# msc3102.net
KiCad netlist of a schematic drawn in EAGLE
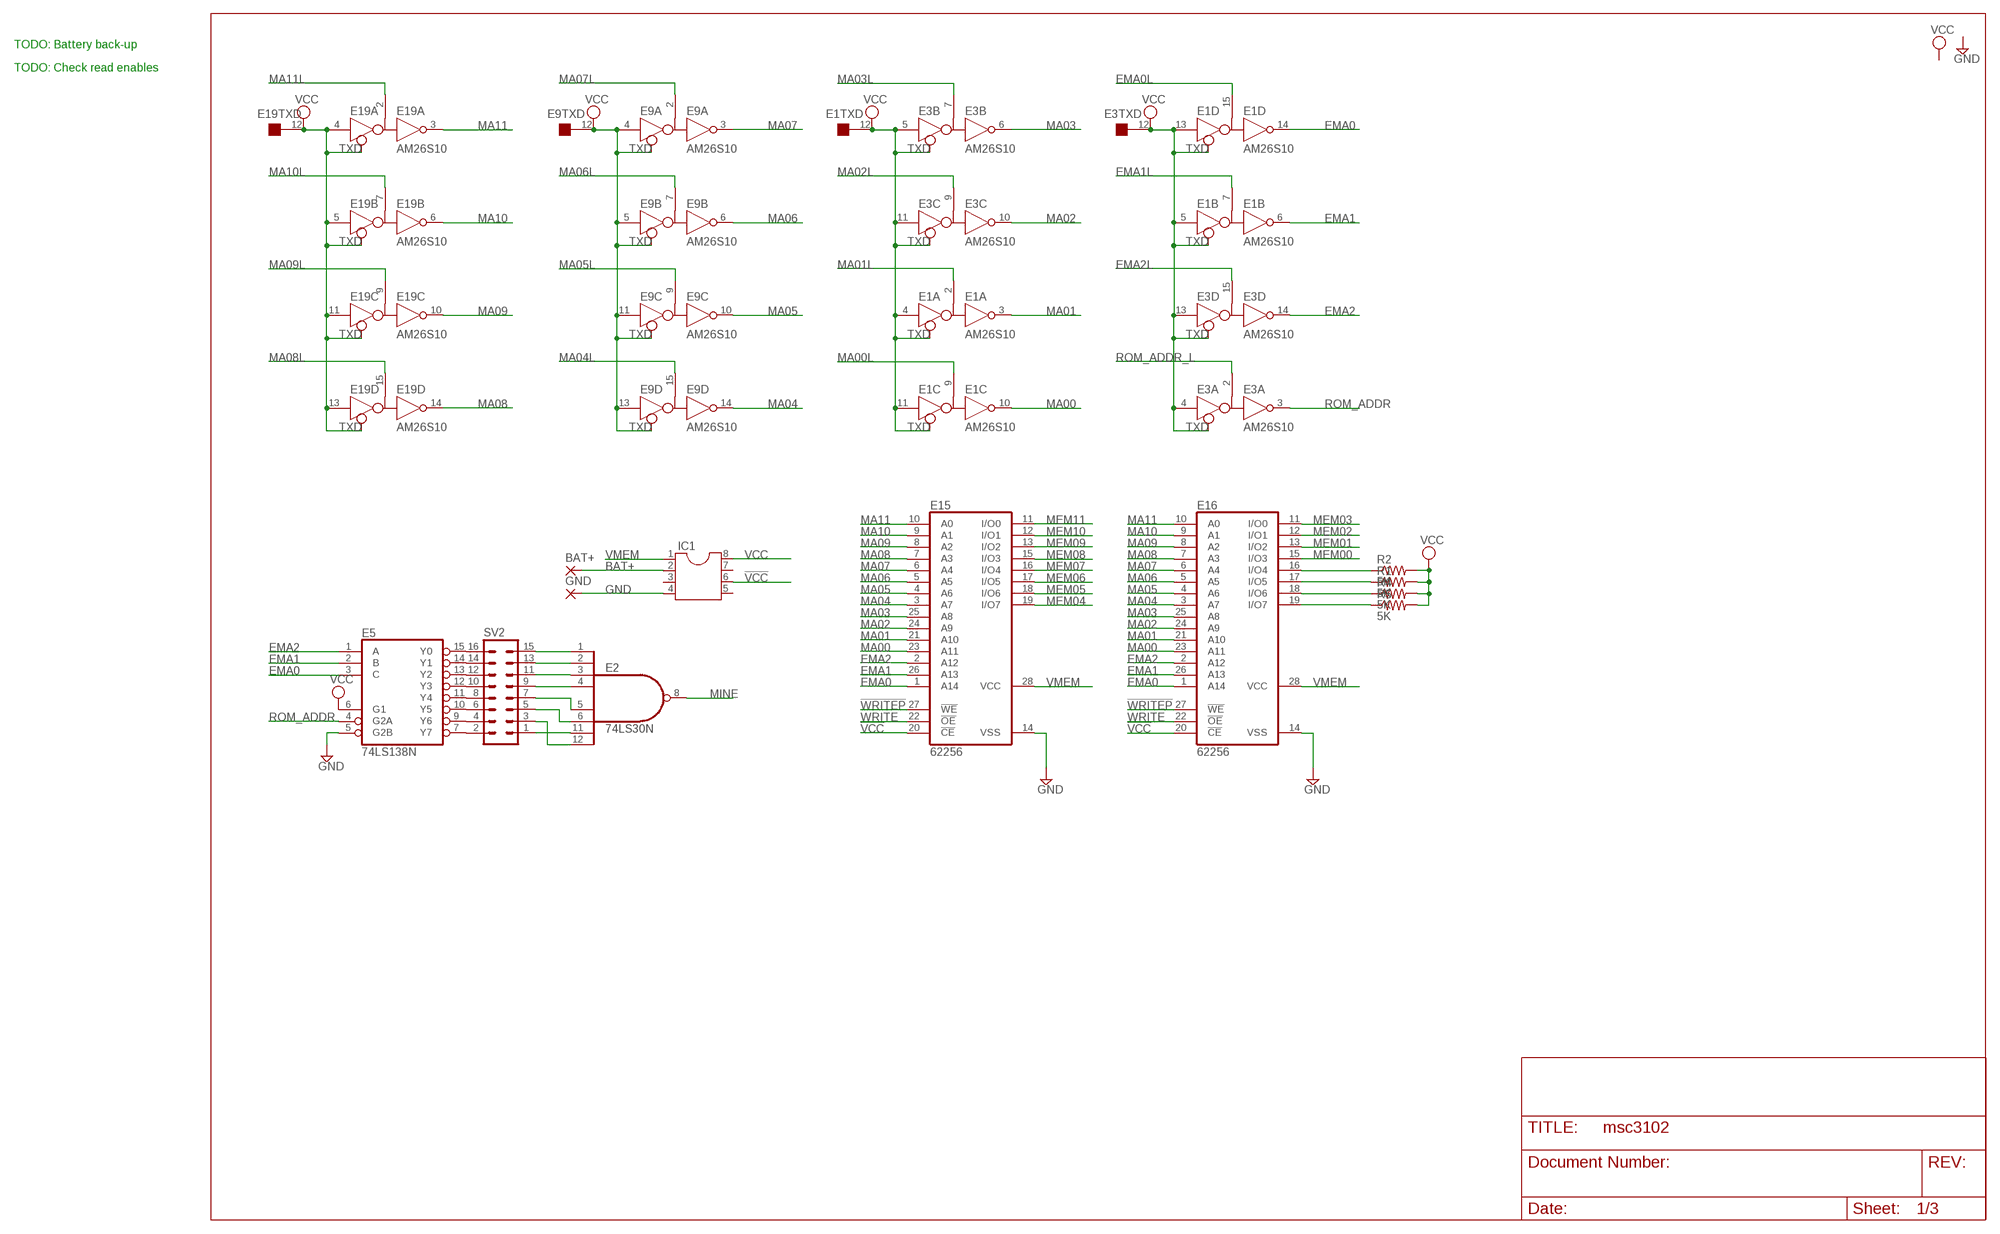
[diagram p0: schematic, sheet 1]
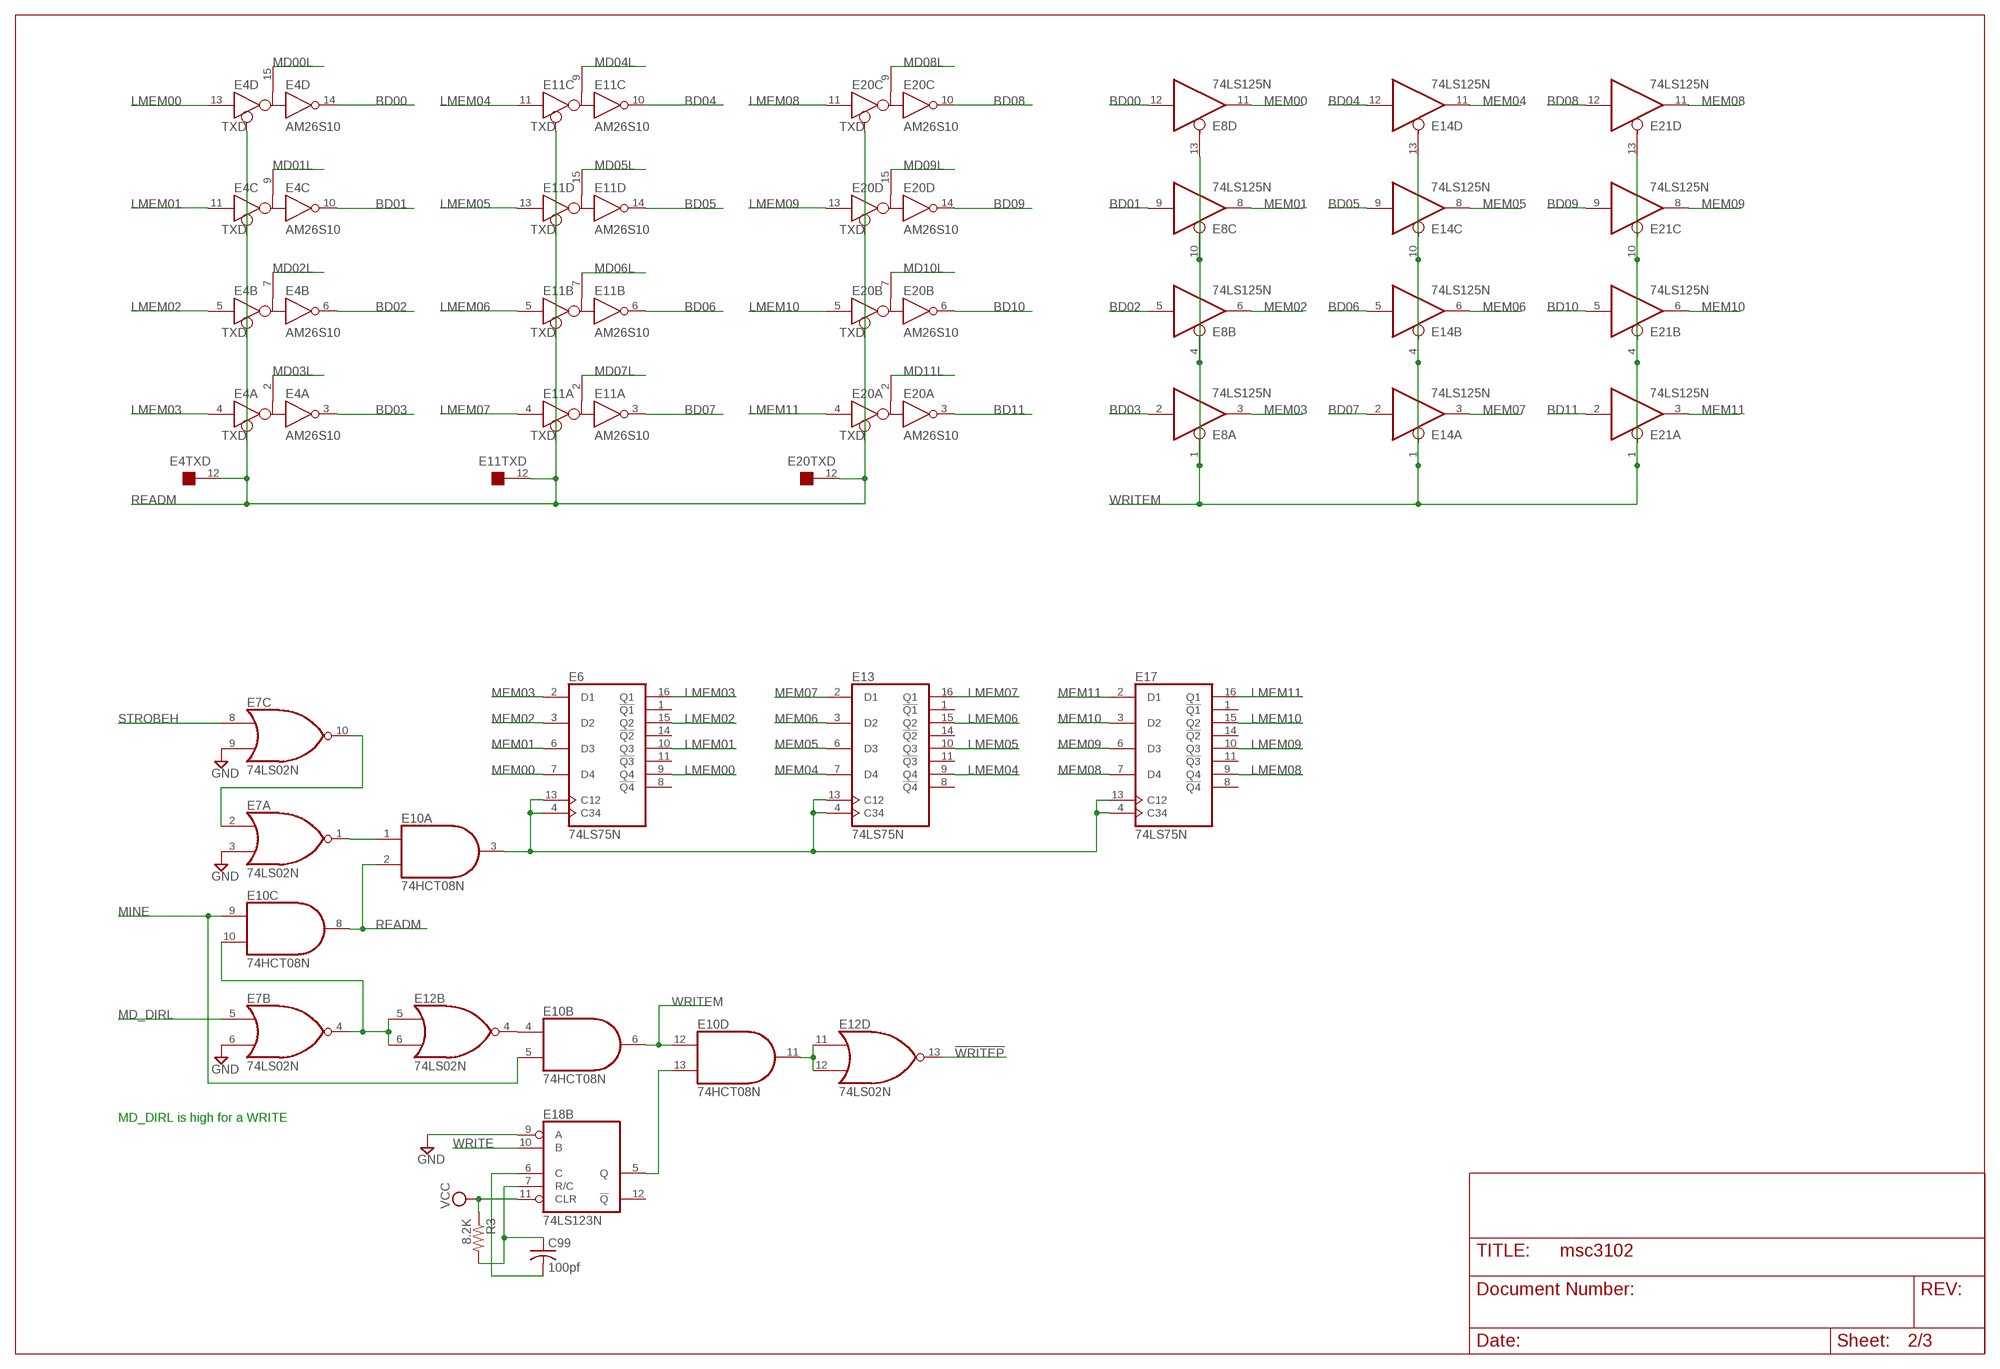
[diagram p1: schematic, sheet 2]
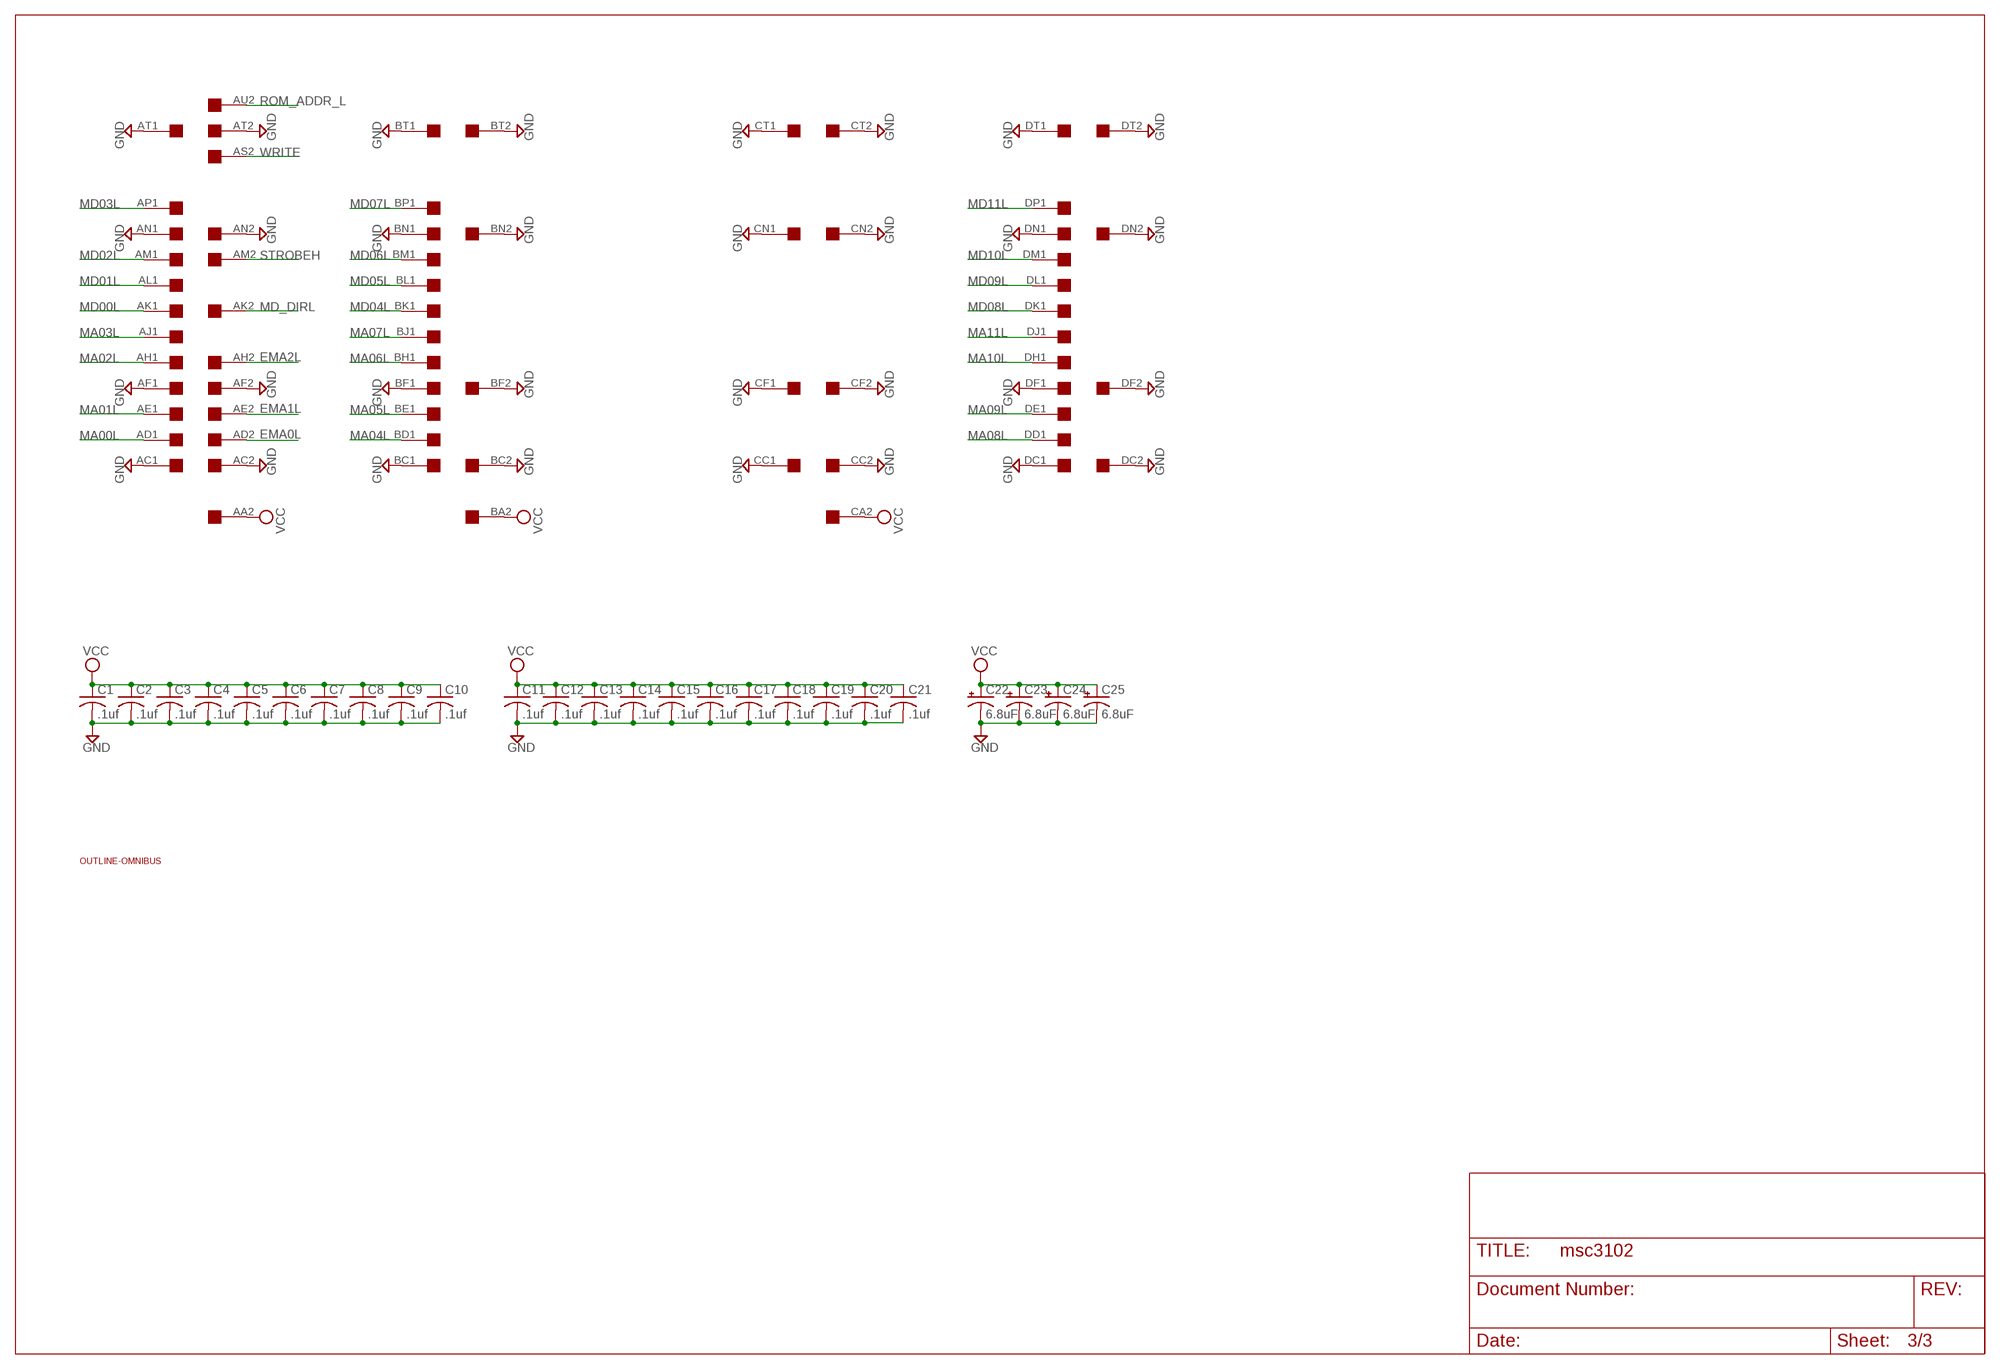
[diagram p2: schematic, sheet 3]

(export (version "E")
  (design (tool "Eeschema 10.0.6"))
  (components
    (comp (ref "C99")
      (value "100pf")
      (footprint "eagle-import:C050-025X075")
      (libsource (lib "eagle-import") (part "C-US050-025X075"))
    )
    (comp (ref "E4")
      (value "AM26S10")
      (footprint "eagle-import:DIL16")
      (libsource (lib "eagle-import") (part "AM26S10"))
    )
    (comp (ref "E6")
      (value "74LS75N")
      (footprint "eagle-import:DIL16")
      (libsource (lib "eagle-import") (part "7475NLS"))
    )
    (comp (ref "E7")
      (value "74LS02N")
      (footprint "eagle-import:DIL14")
      (libsource (lib "eagle-import") (part "7402NLS"))
    )
    (comp (ref "E8")
      (value "74LS125N")
      (footprint "eagle-import:DIL14")
      (libsource (lib "eagle-import") (part "74125NLS"))
    )
    (comp (ref "E10")
      (value "74HCT08N")
      (footprint "eagle-import:DIL14")
      (libsource (lib "eagle-import") (part "7408NLS"))
    )
    (comp (ref "E11")
      (value "AM26S10")
      (footprint "eagle-import:DIL16")
      (libsource (lib "eagle-import") (part "AM26S10"))
    )
    (comp (ref "E12")
      (value "74LS02N")
      (footprint "eagle-import:DIL14")
      (libsource (lib "eagle-import") (part "7402NLS"))
    )
    (comp (ref "E13")
      (value "74LS75N")
      (footprint "eagle-import:DIL16")
      (libsource (lib "eagle-import") (part "7475NLS"))
    )
    (comp (ref "E14")
      (value "74LS125N")
      (footprint "eagle-import:DIL14")
      (libsource (lib "eagle-import") (part "74125NLS"))
    )
    (comp (ref "E17")
      (value "74LS75N")
      (footprint "eagle-import:DIL16")
      (libsource (lib "eagle-import") (part "7475NLS"))
    )
    (comp (ref "E18")
      (value "74LS123N")
      (footprint "eagle-import:DIL16")
      (libsource (lib "eagle-import") (part "74123NLS"))
    )
    (comp (ref "E20")
      (value "AM26S10")
      (footprint "eagle-import:DIL16")
      (libsource (lib "eagle-import") (part "AM26S10"))
    )
    (comp (ref "E21")
      (value "74LS125N")
      (footprint "eagle-import:DIL14")
      (libsource (lib "eagle-import") (part "74125NLS"))
    )
    (comp (ref "R3")
      (value "8.2K")
      (footprint "eagle-import:0207_10")
      (libsource (lib "eagle-import") (part "R-US_0207/10"))
    )
    (comp (ref "BAT+")
      (value "2,15/1,0")
      (footprint "eagle-import:2,15_1,0")
      (libsource (lib "eagle-import") (part "2,15/1,0"))
    )
    (comp (ref "E1")
      (value "AM26S10")
      (footprint "eagle-import:DIL16")
      (libsource (lib "eagle-import") (part "AM26S10"))
    )
    (comp (ref "E2")
      (value "74LS30N")
      (footprint "eagle-import:DIL14")
      (libsource (lib "eagle-import") (part "7430NLS"))
    )
    (comp (ref "E3")
      (value "AM26S10")
      (footprint "eagle-import:DIL16")
      (libsource (lib "eagle-import") (part "AM26S10"))
    )
    (comp (ref "E5")
      (value "74LS138N")
      (footprint "eagle-import:DIL16")
      (libsource (lib "eagle-import") (part "74138NLS"))
    )
    (comp (ref "E9")
      (value "AM26S10")
      (footprint "eagle-import:DIL16")
      (libsource (lib "eagle-import") (part "AM26S10"))
    )
    (comp (ref "E15")
      (value "62256")
      (footprint "eagle-import:DIL28-6")
      (fields (field (name "MPN") "HN58C256AP85E"))
      (libsource (lib "eagle-import") (part "58C256P"))
    )
    (comp (ref "E16")
      (value "62256")
      (footprint "eagle-import:DIL28-6")
      (fields (field (name "MPN") "HN58C256AP85E"))
      (libsource (lib "eagle-import") (part "58C256P"))
    )
    (comp (ref "E19")
      (value "AM26S10")
      (footprint "eagle-import:DIL16")
      (libsource (lib "eagle-import") (part "AM26S10"))
    )
    (comp (ref "GND")
      (value "2,15/1,0")
      (footprint "eagle-import:2,15_1,0")
      (libsource (lib "eagle-import") (part "2,15/1,0"))
    )
    (comp (ref "IC1")
      (value "DIL8")
      (footprint "eagle-import:DIL08")
      (libsource (lib "eagle-import") (part "DIL8"))
    )
    (comp (ref "R1")
      (value "5K")
      (footprint "eagle-import:0207_10")
      (libsource (lib "eagle-import") (part "R-US_0207/10"))
    )
    (comp (ref "R2")
      (value "5K")
      (footprint "eagle-import:0207_10")
      (libsource (lib "eagle-import") (part "R-US_0207/10"))
    )
    (comp (ref "R4")
      (value "5K")
      (footprint "eagle-import:0207_10")
      (libsource (lib "eagle-import") (part "R-US_0207/10"))
    )
    (comp (ref "R5")
      (value "5K")
      (footprint "eagle-import:0207_10")
      (libsource (lib "eagle-import") (part "R-US_0207/10"))
    )
    (comp (ref "SV2")
      (value "MA08-2")
      (footprint "eagle-import:MA08-2")
      (libsource (lib "eagle-import") (part "MA08-2"))
    )
    (comp (ref "C1")
      (value ".1uf")
      (footprint "eagle-import:C050-025X075")
      (libsource (lib "eagle-import") (part "C-US050-025X075"))
    )
    (comp (ref "C2")
      (value ".1uf")
      (footprint "eagle-import:C050-025X075")
      (libsource (lib "eagle-import") (part "C-US050-025X075"))
    )
    (comp (ref "C3")
      (value ".1uf")
      (footprint "eagle-import:C050-025X075")
      (libsource (lib "eagle-import") (part "C-US050-025X075"))
    )
    (comp (ref "C4")
      (value ".1uf")
      (footprint "eagle-import:C050-025X075")
      (libsource (lib "eagle-import") (part "C-US050-025X075"))
    )
    (comp (ref "C5")
      (value ".1uf")
      (footprint "eagle-import:C050-025X075")
      (libsource (lib "eagle-import") (part "C-US050-025X075"))
    )
    (comp (ref "C6")
      (value ".1uf")
      (footprint "eagle-import:C050-025X075")
      (libsource (lib "eagle-import") (part "C-US050-025X075"))
    )
    (comp (ref "C7")
      (value ".1uf")
      (footprint "eagle-import:C050-025X075")
      (libsource (lib "eagle-import") (part "C-US050-025X075"))
    )
    (comp (ref "C8")
      (value ".1uf")
      (footprint "eagle-import:C050-025X075")
      (libsource (lib "eagle-import") (part "C-US050-025X075"))
    )
    (comp (ref "C9")
      (value ".1uf")
      (footprint "eagle-import:C050-025X075")
      (libsource (lib "eagle-import") (part "C-US050-025X075"))
    )
    (comp (ref "C10")
      (value ".1uf")
      (footprint "eagle-import:C050-025X075")
      (libsource (lib "eagle-import") (part "C-US050-025X075"))
    )
    (comp (ref "C11")
      (value ".1uf")
      (footprint "eagle-import:C050-025X075")
      (libsource (lib "eagle-import") (part "C-US050-025X075"))
    )
    (comp (ref "C12")
      (value ".1uf")
      (footprint "eagle-import:C050-025X075")
      (libsource (lib "eagle-import") (part "C-US050-025X075"))
    )
    (comp (ref "C13")
      (value ".1uf")
      (footprint "eagle-import:C050-025X075")
      (libsource (lib "eagle-import") (part "C-US050-025X075"))
    )
    (comp (ref "C14")
      (value ".1uf")
      (footprint "eagle-import:C050-025X075")
      (libsource (lib "eagle-import") (part "C-US050-025X075"))
    )
    (comp (ref "C15")
      (value ".1uf")
      (footprint "eagle-import:C050-025X075")
      (libsource (lib "eagle-import") (part "C-US050-025X075"))
    )
    (comp (ref "C16")
      (value ".1uf")
      (footprint "eagle-import:C050-025X075")
      (libsource (lib "eagle-import") (part "C-US050-025X075"))
    )
    (comp (ref "C17")
      (value ".1uf")
      (footprint "eagle-import:C050-025X075")
      (libsource (lib "eagle-import") (part "C-US050-025X075"))
    )
    (comp (ref "C18")
      (value ".1uf")
      (footprint "eagle-import:C050-025X075")
      (libsource (lib "eagle-import") (part "C-US050-025X075"))
    )
    (comp (ref "C19")
      (value ".1uf")
      (footprint "eagle-import:C050-025X075")
      (libsource (lib "eagle-import") (part "C-US050-025X075"))
    )
    (comp (ref "C20")
      (value ".1uf")
      (footprint "eagle-import:C050-025X075")
      (libsource (lib "eagle-import") (part "C-US050-025X075"))
    )
    (comp (ref "C21")
      (value ".1uf")
      (footprint "eagle-import:C050-025X075")
      (libsource (lib "eagle-import") (part "C-US050-025X075"))
    )
    (comp (ref "C22")
      (value "6.8uF")
      (footprint "eagle-import:E22-6")
      (libsource (lib "eagle-import") (part "CPOL-USE22-6AXIAL"))
    )
    (comp (ref "C23")
      (value "6.8uF")
      (footprint "eagle-import:E22-6")
      (libsource (lib "eagle-import") (part "CPOL-USE22-6AXIAL"))
    )
    (comp (ref "C24")
      (value "6.8uF")
      (footprint "eagle-import:E22-6")
      (libsource (lib "eagle-import") (part "CPOL-USE22-6AXIAL"))
    )
    (comp (ref "C25")
      (value "6.8uF")
      (footprint "eagle-import:E22-6")
      (libsource (lib "eagle-import") (part "CPOL-USE22-6AXIAL"))
    )
    (comp (ref "U$1")
      (value "OUTLINE-OMNIBUS")
      (footprint "eagle-import:OMNIBUS")
      (libsource (lib "eagle-import") (part "OUTLINE-OMNIBUS"))
    )
    (comp (ref "U$2")
      (value "QUAD")
      (footprint "eagle-import:EDGE-CON8")
      (libsource (lib "eagle-import") (part "QUAD"))
    )
  )
  (nets
    (net (code "1") (name "BAT+") (class "Default")
      (node (ref "BAT+") (pin "1") (pinfunction "P_1") (pintype "passive"))
      (node (ref "IC1") (pin "2") (pinfunction "2_2") (pintype "passive"))
    )
    (net (code "2") (name "BD00") (class "Default")
      (node (ref "E4") (pin "14") (pinfunction "R_14") (pintype "output"))
      (node (ref "E8") (pin "12") (pinfunction "I_12") (pintype "input"))
    )
    (net (code "3") (name "BD01") (class "Default")
      (node (ref "E4") (pin "10") (pinfunction "R_10") (pintype "output"))
      (node (ref "E8") (pin "9") (pinfunction "I_9") (pintype "input"))
    )
    (net (code "4") (name "BD02") (class "Default")
      (node (ref "E4") (pin "6") (pinfunction "R_6") (pintype "output"))
      (node (ref "E8") (pin "5") (pinfunction "I_5") (pintype "input"))
    )
    (net (code "5") (name "BD03") (class "Default")
      (node (ref "E4") (pin "3") (pinfunction "R_3") (pintype "output"))
      (node (ref "E8") (pin "2") (pinfunction "I_2") (pintype "input"))
    )
    (net (code "6") (name "BD04") (class "Default")
      (node (ref "E11") (pin "10") (pinfunction "R_10") (pintype "output"))
      (node (ref "E14") (pin "12") (pinfunction "I_12") (pintype "input"))
    )
    (net (code "7") (name "BD05") (class "Default")
      (node (ref "E11") (pin "14") (pinfunction "R_14") (pintype "output"))
      (node (ref "E14") (pin "9") (pinfunction "I_9") (pintype "input"))
    )
    (net (code "8") (name "BD06") (class "Default")
      (node (ref "E11") (pin "6") (pinfunction "R_6") (pintype "output"))
      (node (ref "E14") (pin "5") (pinfunction "I_5") (pintype "input"))
    )
    (net (code "9") (name "BD07") (class "Default")
      (node (ref "E11") (pin "3") (pinfunction "R_3") (pintype "output"))
      (node (ref "E14") (pin "2") (pinfunction "I_2") (pintype "input"))
    )
    (net (code "10") (name "BD08") (class "Default")
      (node (ref "E20") (pin "10") (pinfunction "R_10") (pintype "output"))
      (node (ref "E21") (pin "12") (pinfunction "I_12") (pintype "input"))
    )
    (net (code "11") (name "BD09") (class "Default")
      (node (ref "E20") (pin "14") (pinfunction "R_14") (pintype "output"))
      (node (ref "E21") (pin "9") (pinfunction "I_9") (pintype "input"))
    )
    (net (code "12") (name "BD10") (class "Default")
      (node (ref "E20") (pin "6") (pinfunction "R_6") (pintype "output"))
      (node (ref "E21") (pin "5") (pinfunction "I_5") (pintype "input"))
    )
    (net (code "13") (name "BD11") (class "Default")
      (node (ref "E20") (pin "3") (pinfunction "R_3") (pintype "output"))
      (node (ref "E21") (pin "2") (pinfunction "I_2") (pintype "input"))
    )
    (net (code "14") (name "EMA0") (class "Default")
      (node (ref "E1") (pin "14") (pinfunction "R_14") (pintype "output"))
      (node (ref "E15") (pin "1") (pinfunction "A14_1") (pintype "input"))
      (node (ref "E16") (pin "1") (pinfunction "A14_1") (pintype "input"))
      (node (ref "E5") (pin "3") (pinfunction "C_3") (pintype "input"))
    )
    (net (code "15") (name "EMA0L") (class "Default")
      (node (ref "E1") (pin "15") (pinfunction "B_15") (pintype "bidirectional"))
      (node (ref "U$2") (pin "AD2") (pinfunction "1_AD2") (pintype "bidirectional"))
    )
    (net (code "16") (name "EMA1") (class "Default")
      (node (ref "E1") (pin "6") (pinfunction "R_6") (pintype "output"))
      (node (ref "E15") (pin "26") (pinfunction "A13_26") (pintype "input"))
      (node (ref "E16") (pin "26") (pinfunction "A13_26") (pintype "input"))
      (node (ref "E5") (pin "2") (pinfunction "B_2") (pintype "input"))
    )
    (net (code "17") (name "EMA1L") (class "Default")
      (node (ref "E1") (pin "7") (pinfunction "B_7") (pintype "bidirectional"))
      (node (ref "U$2") (pin "AE2") (pinfunction "1_AE2") (pintype "bidirectional"))
    )
    (net (code "18") (name "EMA2") (class "Default")
      (node (ref "E15") (pin "2") (pinfunction "A12_2") (pintype "input"))
      (node (ref "E16") (pin "2") (pinfunction "A12_2") (pintype "input"))
      (node (ref "E3") (pin "14") (pinfunction "R_14") (pintype "output"))
      (node (ref "E5") (pin "1") (pinfunction "A_1") (pintype "input"))
    )
    (net (code "19") (name "EMA2L") (class "Default")
      (node (ref "E3") (pin "15") (pinfunction "B_15") (pintype "bidirectional"))
      (node (ref "U$2") (pin "AH2") (pinfunction "1_AH2") (pintype "bidirectional"))
    )
    (net (code "20") (name "GND") (class "Default")
      (node (ref "C1") (pin "2") (pinfunction "2_2") (pintype "passive"))
      (node (ref "C10") (pin "2") (pinfunction "2_2") (pintype "passive"))
      (node (ref "C11") (pin "2") (pinfunction "2_2") (pintype "passive"))
      (node (ref "C12") (pin "2") (pinfunction "2_2") (pintype "passive"))
      (node (ref "C13") (pin "2") (pinfunction "2_2") (pintype "passive"))
      (node (ref "C14") (pin "2") (pinfunction "2_2") (pintype "passive"))
      (node (ref "C15") (pin "2") (pinfunction "2_2") (pintype "passive"))
      (node (ref "C16") (pin "2") (pinfunction "2_2") (pintype "passive"))
      (node (ref "C17") (pin "2") (pinfunction "2_2") (pintype "passive"))
      (node (ref "C18") (pin "2") (pinfunction "2_2") (pintype "passive"))
      (node (ref "C19") (pin "2") (pinfunction "2_2") (pintype "passive"))
      (node (ref "C2") (pin "2") (pinfunction "2_2") (pintype "passive"))
      (node (ref "C20") (pin "2") (pinfunction "2_2") (pintype "passive"))
      (node (ref "C21") (pin "2") (pinfunction "2_2") (pintype "passive"))
      (node (ref "C22") (pin "-") (pinfunction "-_-") (pintype "passive"))
      (node (ref "C23") (pin "-") (pinfunction "-_-") (pintype "passive"))
      (node (ref "C24") (pin "-") (pinfunction "-_-") (pintype "passive"))
      (node (ref "C25") (pin "-") (pinfunction "-_-") (pintype "passive"))
      (node (ref "C3") (pin "2") (pinfunction "2_2") (pintype "passive"))
      (node (ref "C4") (pin "2") (pinfunction "2_2") (pintype "passive"))
      (node (ref "C5") (pin "2") (pinfunction "2_2") (pintype "passive"))
      (node (ref "C6") (pin "2") (pinfunction "2_2") (pintype "passive"))
      (node (ref "C7") (pin "2") (pinfunction "2_2") (pintype "passive"))
      (node (ref "C8") (pin "2") (pinfunction "2_2") (pintype "passive"))
      (node (ref "C9") (pin "2") (pinfunction "2_2") (pintype "passive"))
      (node (ref "E15") (pin "14") (pinfunction "VSS_14") (pintype "power_in"))
      (node (ref "E16") (pin "14") (pinfunction "VSS_14") (pintype "power_in"))
      (node (ref "E18") (pin "9") (pinfunction "A_9") (pintype "input"))
      (node (ref "E5") (pin "5") (pinfunction "G2B_5") (pintype "input"))
      (node (ref "E7") (pin "3") (pinfunction "I1_3") (pintype "input"))
      (node (ref "E7") (pin "6") (pinfunction "I1_6") (pintype "input"))
      (node (ref "E7") (pin "9") (pinfunction "I1_9") (pintype "input"))
      (node (ref "GND") (pin "1") (pinfunction "P_1") (pintype "passive"))
      (node (ref "IC1") (pin "4") (pinfunction "4_4") (pintype "passive"))
      (node (ref "U$2") (pin "AC1") (pinfunction "1_AC1") (pintype "bidirectional"))
      (node (ref "U$2") (pin "AC2") (pinfunction "1_AC2") (pintype "bidirectional"))
      (node (ref "U$2") (pin "AF1") (pinfunction "1_AF1") (pintype "bidirectional"))
      (node (ref "U$2") (pin "AF2") (pinfunction "1_AF2") (pintype "bidirectional"))
      (node (ref "U$2") (pin "AN1") (pinfunction "1_AN1") (pintype "bidirectional"))
      (node (ref "U$2") (pin "AN2") (pinfunction "1_AN2") (pintype "bidirectional"))
      (node (ref "U$2") (pin "AT1") (pinfunction "1_AT1") (pintype "bidirectional"))
      (node (ref "U$2") (pin "AT2") (pinfunction "1_AT2") (pintype "bidirectional"))
      (node (ref "U$2") (pin "BC1") (pinfunction "1_BC1") (pintype "bidirectional"))
      (node (ref "U$2") (pin "BC2") (pinfunction "1_BC2") (pintype "bidirectional"))
      (node (ref "U$2") (pin "BF1") (pinfunction "1_BF1") (pintype "bidirectional"))
      (node (ref "U$2") (pin "BF2") (pinfunction "1_BF2") (pintype "bidirectional"))
      (node (ref "U$2") (pin "BN1") (pinfunction "1_BN1") (pintype "bidirectional"))
      (node (ref "U$2") (pin "BN2") (pinfunction "1_BN2") (pintype "bidirectional"))
      (node (ref "U$2") (pin "BT1") (pinfunction "1_BT1") (pintype "bidirectional"))
      (node (ref "U$2") (pin "BT2") (pinfunction "1_BT2") (pintype "bidirectional"))
      (node (ref "U$2") (pin "CC1") (pinfunction "1_CC1") (pintype "bidirectional"))
      (node (ref "U$2") (pin "CC2") (pinfunction "1_CC2") (pintype "bidirectional"))
      (node (ref "U$2") (pin "CF1") (pinfunction "1_CF1") (pintype "bidirectional"))
      (node (ref "U$2") (pin "CF2") (pinfunction "1_CF2") (pintype "bidirectional"))
      (node (ref "U$2") (pin "CN1") (pinfunction "1_CN1") (pintype "bidirectional"))
      (node (ref "U$2") (pin "CN2") (pinfunction "1_CN2") (pintype "bidirectional"))
      (node (ref "U$2") (pin "CT1") (pinfunction "1_CT1") (pintype "bidirectional"))
      (node (ref "U$2") (pin "CT2") (pinfunction "1_CT2") (pintype "bidirectional"))
      (node (ref "U$2") (pin "DC1") (pinfunction "1_DC1") (pintype "bidirectional"))
      (node (ref "U$2") (pin "DC2") (pinfunction "1_DC2") (pintype "bidirectional"))
      (node (ref "U$2") (pin "DF1") (pinfunction "1_DF1") (pintype "bidirectional"))
      (node (ref "U$2") (pin "DF2") (pinfunction "1_DF2") (pintype "bidirectional"))
      (node (ref "U$2") (pin "DN1") (pinfunction "1_DN1") (pintype "bidirectional"))
      (node (ref "U$2") (pin "DN2") (pinfunction "1_DN2") (pintype "bidirectional"))
      (node (ref "U$2") (pin "DT1") (pinfunction "1_DT1") (pintype "bidirectional"))
      (node (ref "U$2") (pin "DT2") (pinfunction "1_DT2") (pintype "bidirectional"))
    )
    (net (code "21") (name "LMEM00") (class "Default")
      (node (ref "E4") (pin "13") (pinfunction "D_13") (pintype "input"))
      (node (ref "E6") (pin "9") (pinfunction "Q4_9") (pintype "output"))
    )
    (net (code "22") (name "LMEM01") (class "Default")
      (node (ref "E4") (pin "11") (pinfunction "D_11") (pintype "input"))
      (node (ref "E6") (pin "10") (pinfunction "Q3_10") (pintype "output"))
    )
    (net (code "23") (name "LMEM02") (class "Default")
      (node (ref "E4") (pin "5") (pinfunction "D_5") (pintype "input"))
      (node (ref "E6") (pin "15") (pinfunction "Q2_15") (pintype "output"))
    )
    (net (code "24") (name "LMEM03") (class "Default")
      (node (ref "E4") (pin "4") (pinfunction "D_4") (pintype "input"))
      (node (ref "E6") (pin "16") (pinfunction "Q1_16") (pintype "output"))
    )
    (net (code "25") (name "LMEM04") (class "Default")
      (node (ref "E11") (pin "11") (pinfunction "D_11") (pintype "input"))
      (node (ref "E13") (pin "9") (pinfunction "Q4_9") (pintype "output"))
    )
    (net (code "26") (name "LMEM05") (class "Default")
      (node (ref "E11") (pin "13") (pinfunction "D_13") (pintype "input"))
      (node (ref "E13") (pin "10") (pinfunction "Q3_10") (pintype "output"))
    )
    (net (code "27") (name "LMEM06") (class "Default")
      (node (ref "E11") (pin "5") (pinfunction "D_5") (pintype "input"))
      (node (ref "E13") (pin "15") (pinfunction "Q2_15") (pintype "output"))
    )
    (net (code "28") (name "LMEM07") (class "Default")
      (node (ref "E11") (pin "4") (pinfunction "D_4") (pintype "input"))
      (node (ref "E13") (pin "16") (pinfunction "Q1_16") (pintype "output"))
    )
    (net (code "29") (name "LMEM08") (class "Default")
      (node (ref "E17") (pin "9") (pinfunction "Q4_9") (pintype "output"))
      (node (ref "E20") (pin "11") (pinfunction "D_11") (pintype "input"))
    )
    (net (code "30") (name "LMEM09") (class "Default")
      (node (ref "E17") (pin "10") (pinfunction "Q3_10") (pintype "output"))
      (node (ref "E20") (pin "13") (pinfunction "D_13") (pintype "input"))
    )
    (net (code "31") (name "LMEM10") (class "Default")
      (node (ref "E17") (pin "15") (pinfunction "Q2_15") (pintype "output"))
      (node (ref "E20") (pin "5") (pinfunction "D_5") (pintype "input"))
    )
    (net (code "32") (name "LMEM11") (class "Default")
      (node (ref "E17") (pin "16") (pinfunction "Q1_16") (pintype "output"))
      (node (ref "E20") (pin "4") (pinfunction "D_4") (pintype "input"))
    )
    (net (code "33") (name "MA00") (class "Default")
      (node (ref "E1") (pin "10") (pinfunction "R_10") (pintype "output"))
      (node (ref "E15") (pin "23") (pinfunction "A11_23") (pintype "input"))
      (node (ref "E16") (pin "23") (pinfunction "A11_23") (pintype "input"))
    )
    (net (code "34") (name "MA00L") (class "Default")
      (node (ref "E1") (pin "9") (pinfunction "B_9") (pintype "bidirectional"))
      (node (ref "U$2") (pin "AD1") (pinfunction "1_AD1") (pintype "bidirectional"))
    )
    (net (code "35") (name "MA01") (class "Default")
      (node (ref "E1") (pin "3") (pinfunction "R_3") (pintype "output"))
      (node (ref "E15") (pin "21") (pinfunction "A10_21") (pintype "input"))
      (node (ref "E16") (pin "21") (pinfunction "A10_21") (pintype "input"))
    )
    (net (code "36") (name "MA01L") (class "Default")
      (node (ref "E1") (pin "2") (pinfunction "B_2") (pintype "bidirectional"))
      (node (ref "U$2") (pin "AE1") (pinfunction "1_AE1") (pintype "bidirectional"))
    )
    (net (code "37") (name "MA02") (class "Default")
      (node (ref "E15") (pin "24") (pinfunction "A9_24") (pintype "input"))
      (node (ref "E16") (pin "24") (pinfunction "A9_24") (pintype "input"))
      (node (ref "E3") (pin "10") (pinfunction "R_10") (pintype "output"))
    )
    (net (code "38") (name "MA02L") (class "Default")
      (node (ref "E3") (pin "9") (pinfunction "B_9") (pintype "bidirectional"))
      (node (ref "U$2") (pin "AH1") (pinfunction "1_AH1") (pintype "bidirectional"))
    )
    (net (code "39") (name "MA03") (class "Default")
      (node (ref "E15") (pin "25") (pinfunction "A8_25") (pintype "input"))
      (node (ref "E16") (pin "25") (pinfunction "A8_25") (pintype "input"))
      (node (ref "E3") (pin "6") (pinfunction "R_6") (pintype "output"))
    )
    (net (code "40") (name "MA03L") (class "Default")
      (node (ref "E3") (pin "7") (pinfunction "B_7") (pintype "bidirectional"))
      (node (ref "U$2") (pin "AJ1") (pinfunction "1_AJ1") (pintype "bidirectional"))
    )
    (net (code "41") (name "MA04") (class "Default")
      (node (ref "E15") (pin "3") (pinfunction "A7_3") (pintype "input"))
      (node (ref "E16") (pin "3") (pinfunction "A7_3") (pintype "input"))
      (node (ref "E9") (pin "14") (pinfunction "R_14") (pintype "output"))
    )
    (net (code "42") (name "MA04L") (class "Default")
      (node (ref "E9") (pin "15") (pinfunction "B_15") (pintype "bidirectional"))
      (node (ref "U$2") (pin "BD1") (pinfunction "1_BD1") (pintype "bidirectional"))
    )
    (net (code "43") (name "MA05") (class "Default")
      (node (ref "E15") (pin "4") (pinfunction "A6_4") (pintype "input"))
      (node (ref "E16") (pin "4") (pinfunction "A6_4") (pintype "input"))
      (node (ref "E9") (pin "10") (pinfunction "R_10") (pintype "output"))
    )
    (net (code "44") (name "MA05L") (class "Default")
      (node (ref "E9") (pin "9") (pinfunction "B_9") (pintype "bidirectional"))
      (node (ref "U$2") (pin "BE1") (pinfunction "1_BE1") (pintype "bidirectional"))
    )
    (net (code "45") (name "MA06") (class "Default")
      (node (ref "E15") (pin "5") (pinfunction "A5_5") (pintype "input"))
      (node (ref "E16") (pin "5") (pinfunction "A5_5") (pintype "input"))
      (node (ref "E9") (pin "6") (pinfunction "R_6") (pintype "output"))
    )
    (net (code "46") (name "MA06L") (class "Default")
      (node (ref "E9") (pin "7") (pinfunction "B_7") (pintype "bidirectional"))
      (node (ref "U$2") (pin "BH1") (pinfunction "1_BH1") (pintype "bidirectional"))
    )
    (net (code "47") (name "MA07") (class "Default")
      (node (ref "E15") (pin "6") (pinfunction "A4_6") (pintype "input"))
      (node (ref "E16") (pin "6") (pinfunction "A4_6") (pintype "input"))
      (node (ref "E9") (pin "3") (pinfunction "R_3") (pintype "output"))
    )
    (net (code "48") (name "MA07L") (class "Default")
      (node (ref "E9") (pin "2") (pinfunction "B_2") (pintype "bidirectional"))
      (node (ref "U$2") (pin "BJ1") (pinfunction "1_BJ1") (pintype "bidirectional"))
    )
    (net (code "49") (name "MA08") (class "Default")
      (node (ref "E15") (pin "7") (pinfunction "A3_7") (pintype "input"))
      (node (ref "E16") (pin "7") (pinfunction "A3_7") (pintype "input"))
      (node (ref "E19") (pin "14") (pinfunction "R_14") (pintype "output"))
    )
    (net (code "50") (name "MA08L") (class "Default")
      (node (ref "E19") (pin "15") (pinfunction "B_15") (pintype "bidirectional"))
      (node (ref "U$2") (pin "DD1") (pinfunction "1_DD1") (pintype "bidirectional"))
    )
    (net (code "51") (name "MA09") (class "Default")
      (node (ref "E15") (pin "8") (pinfunction "A2_8") (pintype "input"))
      (node (ref "E16") (pin "8") (pinfunction "A2_8") (pintype "input"))
      (node (ref "E19") (pin "10") (pinfunction "R_10") (pintype "output"))
    )
    (net (code "52") (name "MA09L") (class "Default")
      (node (ref "E19") (pin "9") (pinfunction "B_9") (pintype "bidirectional"))
      (node (ref "U$2") (pin "DE1") (pinfunction "1_DE1") (pintype "bidirectional"))
    )
    (net (code "53") (name "MA10") (class "Default")
      (node (ref "E15") (pin "9") (pinfunction "A1_9") (pintype "input"))
      (node (ref "E16") (pin "9") (pinfunction "A1_9") (pintype "input"))
      (node (ref "E19") (pin "6") (pinfunction "R_6") (pintype "output"))
    )
    (net (code "54") (name "MA10L") (class "Default")
      (node (ref "E19") (pin "7") (pinfunction "B_7") (pintype "bidirectional"))
      (node (ref "U$2") (pin "DH1") (pinfunction "1_DH1") (pintype "bidirectional"))
    )
    (net (code "55") (name "MA11") (class "Default")
      (node (ref "E15") (pin "10") (pinfunction "A0_10") (pintype "input"))
      (node (ref "E16") (pin "10") (pinfunction "A0_10") (pintype "input"))
      (node (ref "E19") (pin "3") (pinfunction "R_3") (pintype "output"))
    )
    (net (code "56") (name "MA11L") (class "Default")
      (node (ref "E19") (pin "2") (pinfunction "B_2") (pintype "bidirectional"))
      (node (ref "U$2") (pin "DJ1") (pinfunction "1_DJ1") (pintype "bidirectional"))
    )
    (net (code "57") (name "MD00L") (class "Default")
      (node (ref "E4") (pin "15") (pinfunction "B_15") (pintype "bidirectional"))
      (node (ref "U$2") (pin "AK1") (pinfunction "1_AK1") (pintype "bidirectional"))
    )
    (net (code "58") (name "MD01L") (class "Default")
      (node (ref "E4") (pin "9") (pinfunction "B_9") (pintype "bidirectional"))
      (node (ref "U$2") (pin "AL1") (pinfunction "1_AL1") (pintype "bidirectional"))
    )
    (net (code "59") (name "MD02L") (class "Default")
      (node (ref "E4") (pin "7") (pinfunction "B_7") (pintype "bidirectional"))
      (node (ref "U$2") (pin "AM1") (pinfunction "1_AM1") (pintype "bidirectional"))
    )
    (net (code "60") (name "MD03L") (class "Default")
      (node (ref "E4") (pin "2") (pinfunction "B_2") (pintype "bidirectional"))
      (node (ref "U$2") (pin "AP1") (pinfunction "1_AP1") (pintype "bidirectional"))
    )
    (net (code "61") (name "MD04L") (class "Default")
      (node (ref "E11") (pin "9") (pinfunction "B_9") (pintype "bidirectional"))
      (node (ref "U$2") (pin "BK1") (pinfunction "1_BK1") (pintype "bidirectional"))
    )
    (net (code "62") (name "MD05L") (class "Default")
      (node (ref "E11") (pin "15") (pinfunction "B_15") (pintype "bidirectional"))
      (node (ref "U$2") (pin "BL1") (pinfunction "1_BL1") (pintype "bidirectional"))
    )
    (net (code "63") (name "MD06L") (class "Default")
      (node (ref "E11") (pin "7") (pinfunction "B_7") (pintype "bidirectional"))
      (node (ref "U$2") (pin "BM1") (pinfunction "1_BM1") (pintype "bidirectional"))
    )
    (net (code "64") (name "MD07L") (class "Default")
      (node (ref "E11") (pin "2") (pinfunction "B_2") (pintype "bidirectional"))
      (node (ref "U$2") (pin "BP1") (pinfunction "1_BP1") (pintype "bidirectional"))
    )
    (net (code "65") (name "MD08L") (class "Default")
      (node (ref "E20") (pin "9") (pinfunction "B_9") (pintype "bidirectional"))
      (node (ref "U$2") (pin "DK1") (pinfunction "1_DK1") (pintype "bidirectional"))
    )
    (net (code "66") (name "MD09L") (class "Default")
      (node (ref "E20") (pin "15") (pinfunction "B_15") (pintype "bidirectional"))
      (node (ref "U$2") (pin "DL1") (pinfunction "1_DL1") (pintype "bidirectional"))
    )
    (net (code "67") (name "MD10L") (class "Default")
      (node (ref "E20") (pin "7") (pinfunction "B_7") (pintype "bidirectional"))
      (node (ref "U$2") (pin "DM1") (pinfunction "1_DM1") (pintype "bidirectional"))
    )
    (net (code "68") (name "MD11L") (class "Default")
      (node (ref "E20") (pin "2") (pinfunction "B_2") (pintype "bidirectional"))
      (node (ref "U$2") (pin "DP1") (pinfunction "1_DP1") (pintype "bidirectional"))
    )
    (net (code "69") (name "MD_DIRL") (class "Default")
      (node (ref "E7") (pin "5") (pinfunction "I0_5") (pintype "input"))
      (node (ref "U$2") (pin "AK2") (pinfunction "1_AK2") (pintype "bidirectional"))
    )
    (net (code "70") (name "MEM00") (class "Default")
      (node (ref "E16") (pin "15") (pinfunction "I/O3_15") (pintype "tri_state"))
      (node (ref "E6") (pin "7") (pinfunction "D4_7") (pintype "input"))
      (node (ref "E8") (pin "11") (pinfunction "O_11") (pintype "tri_state"))
    )
    (net (code "71") (name "MEM01") (class "Default")
      (node (ref "E16") (pin "13") (pinfunction "I/O2_13") (pintype "tri_state"))
      (node (ref "E6") (pin "6") (pinfunction "D3_6") (pintype "input"))
      (node (ref "E8") (pin "8") (pinfunction "O_8") (pintype "tri_state"))
    )
    (net (code "72") (name "MEM02") (class "Default")
      (node (ref "E16") (pin "12") (pinfunction "I/O1_12") (pintype "tri_state"))
      (node (ref "E6") (pin "3") (pinfunction "D2_3") (pintype "input"))
      (node (ref "E8") (pin "6") (pinfunction "O_6") (pintype "tri_state"))
    )
    (net (code "73") (name "MEM03") (class "Default")
      (node (ref "E16") (pin "11") (pinfunction "I/O0_11") (pintype "tri_state"))
      (node (ref "E6") (pin "2") (pinfunction "D1_2") (pintype "input"))
      (node (ref "E8") (pin "3") (pinfunction "O_3") (pintype "tri_state"))
    )
    (net (code "74") (name "MEM04") (class "Default")
      (node (ref "E13") (pin "7") (pinfunction "D4_7") (pintype "input"))
      (node (ref "E14") (pin "11") (pinfunction "O_11") (pintype "tri_state"))
      (node (ref "E15") (pin "19") (pinfunction "I/O7_19") (pintype "tri_state"))
    )
    (net (code "75") (name "MEM05") (class "Default")
      (node (ref "E13") (pin "6") (pinfunction "D3_6") (pintype "input"))
      (node (ref "E14") (pin "8") (pinfunction "O_8") (pintype "tri_state"))
      (node (ref "E15") (pin "18") (pinfunction "I/O6_18") (pintype "tri_state"))
    )
    (net (code "76") (name "MEM06") (class "Default")
      (node (ref "E13") (pin "3") (pinfunction "D2_3") (pintype "input"))
      (node (ref "E14") (pin "6") (pinfunction "O_6") (pintype "tri_state"))
      (node (ref "E15") (pin "17") (pinfunction "I/O5_17") (pintype "tri_state"))
    )
    (net (code "77") (name "MEM07") (class "Default")
      (node (ref "E13") (pin "2") (pinfunction "D1_2") (pintype "input"))
      (node (ref "E14") (pin "3") (pinfunction "O_3") (pintype "tri_state"))
      (node (ref "E15") (pin "16") (pinfunction "I/O4_16") (pintype "tri_state"))
    )
    (net (code "78") (name "MEM08") (class "Default")
      (node (ref "E15") (pin "15") (pinfunction "I/O3_15") (pintype "tri_state"))
      (node (ref "E17") (pin "7") (pinfunction "D4_7") (pintype "input"))
      (node (ref "E21") (pin "11") (pinfunction "O_11") (pintype "tri_state"))
    )
    (net (code "79") (name "MEM09") (class "Default")
      (node (ref "E15") (pin "13") (pinfunction "I/O2_13") (pintype "tri_state"))
      (node (ref "E17") (pin "6") (pinfunction "D3_6") (pintype "input"))
      (node (ref "E21") (pin "8") (pinfunction "O_8") (pintype "tri_state"))
    )
    (net (code "80") (name "MEM10") (class "Default")
      (node (ref "E15") (pin "12") (pinfunction "I/O1_12") (pintype "tri_state"))
      (node (ref "E17") (pin "3") (pinfunction "D2_3") (pintype "input"))
      (node (ref "E21") (pin "6") (pinfunction "O_6") (pintype "tri_state"))
    )
    (net (code "81") (name "MEM11") (class "Default")
      (node (ref "E15") (pin "11") (pinfunction "I/O0_11") (pintype "tri_state"))
      (node (ref "E17") (pin "2") (pinfunction "D1_2") (pintype "input"))
      (node (ref "E21") (pin "3") (pinfunction "O_3") (pintype "tri_state"))
    )
    (net (code "82") (name "MINE") (class "Default")
      (node (ref "E10") (pin "5") (pinfunction "I1_5") (pintype "input"))
      (node (ref "E10") (pin "9") (pinfunction "I0_9") (pintype "input"))
      (node (ref "E2") (pin "8") (pinfunction "O_8") (pintype "output"))
    )
    (net (code "83") (name "Net-(E2A-I0)") (class "Default")
      (node (ref "E2") (pin "1") (pinfunction "I0_1") (pintype "input"))
      (node (ref "SV2") (pin "15") (pinfunction "15_15") (pintype "passive"))
    )
    (net (code "84") (name "Net-(E2A-I1)") (class "Default")
      (node (ref "E2") (pin "2") (pinfunction "I1_2") (pintype "input"))
      (node (ref "SV2") (pin "13") (pinfunction "13_13") (pintype "passive"))
    )
    (net (code "85") (name "Net-(E2A-I2)") (class "Default")
      (node (ref "E2") (pin "3") (pinfunction "I2_3") (pintype "input"))
      (node (ref "SV2") (pin "11") (pinfunction "11_11") (pintype "passive"))
    )
    (net (code "86") (name "Net-(E2A-I3)") (class "Default")
      (node (ref "E2") (pin "4") (pinfunction "I3_4") (pintype "input"))
      (node (ref "SV2") (pin "9") (pinfunction "9_9") (pintype "passive"))
    )
    (net (code "87") (name "Net-(E2A-I4)") (class "Default")
      (node (ref "E2") (pin "5") (pinfunction "I4_5") (pintype "input"))
      (node (ref "SV2") (pin "7") (pinfunction "7_7") (pintype "passive"))
    )
    (net (code "88") (name "Net-(E2A-I5)") (class "Default")
      (node (ref "E2") (pin "6") (pinfunction "I5_6") (pintype "input"))
      (node (ref "SV2") (pin "5") (pinfunction "5_5") (pintype "passive"))
    )
    (net (code "89") (name "Net-(E2A-I6)") (class "Default")
      (node (ref "E2") (pin "11") (pinfunction "I6_11") (pintype "input"))
      (node (ref "SV2") (pin "1") (pinfunction "1_1") (pintype "passive"))
    )
    (net (code "90") (name "Net-(E2A-I7)") (class "Default")
      (node (ref "E2") (pin "12") (pinfunction "I7_12") (pintype "input"))
      (node (ref "SV2") (pin "3") (pinfunction "3_3") (pintype "passive"))
    )
    (net (code "91") (name "Net-(E5A-Y0)") (class "Default")
      (node (ref "E5") (pin "15") (pinfunction "Y0_15") (pintype "output"))
      (node (ref "SV2") (pin "16") (pinfunction "16_16") (pintype "passive"))
    )
    (net (code "92") (name "Net-(E5A-Y1)") (class "Default")
      (node (ref "E5") (pin "14") (pinfunction "Y1_14") (pintype "output"))
      (node (ref "SV2") (pin "14") (pinfunction "14_14") (pintype "passive"))
    )
    (net (code "93") (name "Net-(E5A-Y2)") (class "Default")
      (node (ref "E5") (pin "13") (pinfunction "Y2_13") (pintype "output"))
      (node (ref "SV2") (pin "12") (pinfunction "12_12") (pintype "passive"))
    )
    (net (code "94") (name "Net-(E5A-Y3)") (class "Default")
      (node (ref "E5") (pin "12") (pinfunction "Y3_12") (pintype "output"))
      (node (ref "SV2") (pin "10") (pinfunction "10_10") (pintype "passive"))
    )
    (net (code "95") (name "Net-(E5A-Y4)") (class "Default")
      (node (ref "E5") (pin "11") (pinfunction "Y4_11") (pintype "output"))
      (node (ref "SV2") (pin "8") (pinfunction "8_8") (pintype "passive"))
    )
    (net (code "96") (name "Net-(E5A-Y5)") (class "Default")
      (node (ref "E5") (pin "10") (pinfunction "Y5_10") (pintype "output"))
      (node (ref "SV2") (pin "6") (pinfunction "6_6") (pintype "passive"))
    )
    (net (code "97") (name "Net-(E5A-Y6)") (class "Default")
      (node (ref "E5") (pin "9") (pinfunction "Y6_9") (pintype "output"))
      (node (ref "SV2") (pin "4") (pinfunction "4_4") (pintype "passive"))
    )
    (net (code "98") (name "Net-(E5A-Y7)") (class "Default")
      (node (ref "E5") (pin "7") (pinfunction "Y7_7") (pintype "output"))
      (node (ref "SV2") (pin "2") (pinfunction "2_2") (pintype "passive"))
    )
    (net (code "99") (name "Net-(E7A-I0)") (class "Default")
      (node (ref "E7") (pin "10") (pinfunction "O_10") (pintype "output"))
      (node (ref "E7") (pin "2") (pinfunction "I0_2") (pintype "input"))
    )
    (net (code "100") (name "Net-(E10A-I0)") (class "Default")
      (node (ref "E10") (pin "1") (pinfunction "I0_1") (pintype "input"))
      (node (ref "E7") (pin "1") (pinfunction "O_1") (pintype "output"))
    )
    (net (code "101") (name "Net-(E10A-O)") (class "Default")
      (node (ref "E10") (pin "3") (pinfunction "O_3") (pintype "output"))
      (node (ref "E13") (pin "13") (pinfunction "C12_13") (pintype "input"))
      (node (ref "E13") (pin "4") (pinfunction "C34_4") (pintype "input"))
      (node (ref "E17") (pin "13") (pinfunction "C12_13") (pintype "input"))
      (node (ref "E17") (pin "4") (pinfunction "C34_4") (pintype "input"))
      (node (ref "E6") (pin "13") (pinfunction "C12_13") (pintype "input"))
      (node (ref "E6") (pin "4") (pinfunction "C34_4") (pintype "input"))
    )
    (net (code "102") (name "Net-(E10B-I0)") (class "Default")
      (node (ref "E10") (pin "4") (pinfunction "I0_4") (pintype "input"))
      (node (ref "E12") (pin "4") (pinfunction "O_4") (pintype "output"))
    )
    (net (code "103") (name "Net-(E10C-I1)") (class "Default")
      (node (ref "E10") (pin "10") (pinfunction "I1_10") (pintype "input"))
      (node (ref "E12") (pin "5") (pinfunction "I0_5") (pintype "input"))
      (node (ref "E12") (pin "6") (pinfunction "I1_6") (pintype "input"))
      (node (ref "E7") (pin "4") (pinfunction "O_4") (pintype "output"))
    )
    (net (code "104") (name "Net-(E10D-I1)") (class "Default")
      (node (ref "E10") (pin "13") (pinfunction "I1_13") (pintype "input"))
      (node (ref "E18") (pin "5") (pinfunction "Q_5") (pintype "output"))
    )
    (net (code "105") (name "Net-(E10D-O)") (class "Default")
      (node (ref "E10") (pin "11") (pinfunction "O_11") (pintype "output"))
      (node (ref "E12") (pin "11") (pinfunction "I0_11") (pintype "input"))
      (node (ref "E12") (pin "12") (pinfunction "I1_12") (pintype "input"))
    )
    (net (code "106") (name "Net-(E16-I{slash}O4)") (class "Default")
      (node (ref "E16") (pin "16") (pinfunction "I/O4_16") (pintype "tri_state"))
      (node (ref "R2") (pin "1") (pinfunction "1_1") (pintype "passive"))
    )
    (net (code "107") (name "Net-(E16-I{slash}O5)") (class "Default")
      (node (ref "E16") (pin "17") (pinfunction "I/O5_17") (pintype "tri_state"))
      (node (ref "R1") (pin "1") (pinfunction "1_1") (pintype "passive"))
    )
    (net (code "108") (name "Net-(E16-I{slash}O6)") (class "Default")
      (node (ref "E16") (pin "18") (pinfunction "I/O6_18") (pintype "tri_state"))
      (node (ref "R4") (pin "1") (pinfunction "1_1") (pintype "passive"))
    )
    (net (code "109") (name "Net-(E16-I{slash}O7)") (class "Default")
      (node (ref "E16") (pin "19") (pinfunction "I/O7_19") (pintype "tri_state"))
      (node (ref "R5") (pin "1") (pinfunction "1_1") (pintype "passive"))
    )
    (net (code "110") (name "Net-(E18B-C)") (class "Default")
      (node (ref "C99") (pin "2") (pinfunction "2_2") (pintype "passive"))
      (node (ref "E18") (pin "6") (pinfunction "C_6") (pintype "input"))
    )
    (net (code "111") (name "Net-(E18B-R{slash}C)") (class "Default")
      (node (ref "C99") (pin "1") (pinfunction "1_1") (pintype "passive"))
      (node (ref "E18") (pin "7") (pinfunction "R/C_7") (pintype "input"))
      (node (ref "R3") (pin "2") (pinfunction "2_2") (pintype "passive"))
    )
    (net (code "112") (name "READM") (class "Default")
      (node (ref "E10") (pin "2") (pinfunction "I1_2") (pintype "input"))
      (node (ref "E10") (pin "8") (pinfunction "O_8") (pintype "output"))
      (node (ref "E11") (pin "12") (pinfunction "TXD_12") (pintype "input"))
      (node (ref "E20") (pin "12") (pinfunction "TXD_12") (pintype "input"))
      (node (ref "E4") (pin "12") (pinfunction "TXD_12") (pintype "input"))
    )
    (net (code "113") (name "ROM_ADDR") (class "Default")
      (node (ref "E3") (pin "3") (pinfunction "R_3") (pintype "output"))
      (node (ref "E5") (pin "4") (pinfunction "G2A_4") (pintype "input"))
    )
    (net (code "114") (name "ROM_ADDR_L") (class "Default")
      (node (ref "E3") (pin "2") (pinfunction "B_2") (pintype "bidirectional"))
      (node (ref "U$2") (pin "AU2") (pinfunction "1_AU2") (pintype "bidirectional"))
    )
    (net (code "115") (name "STROBEH") (class "Default")
      (node (ref "E7") (pin "8") (pinfunction "I0_8") (pintype "input"))
      (node (ref "U$2") (pin "AM2") (pinfunction "1_AM2") (pintype "bidirectional"))
    )
    (net (code "116") (name "VCC") (class "Default")
      (node (ref "C1") (pin "1") (pinfunction "1_1") (pintype "passive"))
      (node (ref "C10") (pin "1") (pinfunction "1_1") (pintype "passive"))
      (node (ref "C11") (pin "1") (pinfunction "1_1") (pintype "passive"))
      (node (ref "C12") (pin "1") (pinfunction "1_1") (pintype "passive"))
      (node (ref "C13") (pin "1") (pinfunction "1_1") (pintype "passive"))
      (node (ref "C14") (pin "1") (pinfunction "1_1") (pintype "passive"))
      (node (ref "C15") (pin "1") (pinfunction "1_1") (pintype "passive"))
      (node (ref "C16") (pin "1") (pinfunction "1_1") (pintype "passive"))
      (node (ref "C17") (pin "1") (pinfunction "1_1") (pintype "passive"))
      (node (ref "C18") (pin "1") (pinfunction "1_1") (pintype "passive"))
      (node (ref "C19") (pin "1") (pinfunction "1_1") (pintype "passive"))
      (node (ref "C2") (pin "1") (pinfunction "1_1") (pintype "passive"))
      (node (ref "C20") (pin "1") (pinfunction "1_1") (pintype "passive"))
      (node (ref "C21") (pin "1") (pinfunction "1_1") (pintype "passive"))
      (node (ref "C22") (pin "+") (pinfunction "+_+") (pintype "passive"))
      (node (ref "C23") (pin "+") (pinfunction "+_+") (pintype "passive"))
      (node (ref "C24") (pin "+") (pinfunction "+_+") (pintype "passive"))
      (node (ref "C25") (pin "+") (pinfunction "+_+") (pintype "passive"))
      (node (ref "C3") (pin "1") (pinfunction "1_1") (pintype "passive"))
      (node (ref "C4") (pin "1") (pinfunction "1_1") (pintype "passive"))
      (node (ref "C5") (pin "1") (pinfunction "1_1") (pintype "passive"))
      (node (ref "C6") (pin "1") (pinfunction "1_1") (pintype "passive"))
      (node (ref "C7") (pin "1") (pinfunction "1_1") (pintype "passive"))
      (node (ref "C8") (pin "1") (pinfunction "1_1") (pintype "passive"))
      (node (ref "C9") (pin "1") (pinfunction "1_1") (pintype "passive"))
      (node (ref "E1") (pin "11") (pinfunction "D_11") (pintype "input"))
      (node (ref "E1") (pin "12") (pinfunction "TXD_12") (pintype "input"))
      (node (ref "E1") (pin "13") (pinfunction "D_13") (pintype "input"))
      (node (ref "E1") (pin "4") (pinfunction "D_4") (pintype "input"))
      (node (ref "E1") (pin "5") (pinfunction "D_5") (pintype "input"))
      (node (ref "E18") (pin "11") (pinfunction "CLR_11") (pintype "input"))
      (node (ref "E19") (pin "11") (pinfunction "D_11") (pintype "input"))
      (node (ref "E19") (pin "12") (pinfunction "TXD_12") (pintype "input"))
      (node (ref "E19") (pin "13") (pinfunction "D_13") (pintype "input"))
      (node (ref "E19") (pin "4") (pinfunction "D_4") (pintype "input"))
      (node (ref "E19") (pin "5") (pinfunction "D_5") (pintype "input"))
      (node (ref "E3") (pin "11") (pinfunction "D_11") (pintype "input"))
      (node (ref "E3") (pin "12") (pinfunction "TXD_12") (pintype "input"))
      (node (ref "E3") (pin "13") (pinfunction "D_13") (pintype "input"))
      (node (ref "E3") (pin "4") (pinfunction "D_4") (pintype "input"))
      (node (ref "E3") (pin "5") (pinfunction "D_5") (pintype "input"))
      (node (ref "E5") (pin "6") (pinfunction "G1_6") (pintype "input"))
      (node (ref "E9") (pin "11") (pinfunction "D_11") (pintype "input"))
      (node (ref "E9") (pin "12") (pinfunction "TXD_12") (pintype "input"))
      (node (ref "E9") (pin "13") (pinfunction "D_13") (pintype "input"))
      (node (ref "E9") (pin "4") (pinfunction "D_4") (pintype "input"))
      (node (ref "E9") (pin "5") (pinfunction "D_5") (pintype "input"))
      (node (ref "IC1") (pin "8") (pinfunction "8_8") (pintype "passive"))
      (node (ref "R1") (pin "2") (pinfunction "2_2") (pintype "passive"))
      (node (ref "R2") (pin "2") (pinfunction "2_2") (pintype "passive"))
      (node (ref "R3") (pin "1") (pinfunction "1_1") (pintype "passive"))
      (node (ref "R4") (pin "2") (pinfunction "2_2") (pintype "passive"))
      (node (ref "R5") (pin "2") (pinfunction "2_2") (pintype "passive"))
      (node (ref "U$2") (pin "AA2") (pinfunction "1_AA2") (pintype "bidirectional"))
      (node (ref "U$2") (pin "BA2") (pinfunction "1_BA2") (pintype "bidirectional"))
      (node (ref "U$2") (pin "CA2") (pinfunction "1_CA2") (pintype "bidirectional"))
    )
    (net (code "117") (name "VMEM") (class "Default")
      (node (ref "E15") (pin "28") (pinfunction "VCC_28") (pintype "power_in"))
      (node (ref "E16") (pin "28") (pinfunction "VCC_28") (pintype "power_in"))
      (node (ref "IC1") (pin "1") (pinfunction "1_1") (pintype "passive"))
    )
    (net (code "118") (name "WRITE") (class "Default")
      (node (ref "E15") (pin "22") (pinfunction "~{OE}_22") (pintype "input"))
      (node (ref "E16") (pin "22") (pinfunction "~{OE}_22") (pintype "input"))
      (node (ref "E18") (pin "10") (pinfunction "B_10") (pintype "input"))
      (node (ref "U$2") (pin "AS2") (pinfunction "1_AS2") (pintype "bidirectional"))
    )
    (net (code "119") (name "WRITEM") (class "Default")
      (node (ref "E10") (pin "12") (pinfunction "I0_12") (pintype "input"))
      (node (ref "E10") (pin "6") (pinfunction "O_6") (pintype "output"))
      (node (ref "E14") (pin "1") (pinfunction "OE_1") (pintype "input"))
      (node (ref "E14") (pin "10") (pinfunction "OE_10") (pintype "input"))
      (node (ref "E14") (pin "13") (pinfunction "OE_13") (pintype "input"))
      (node (ref "E14") (pin "4") (pinfunction "OE_4") (pintype "input"))
      (node (ref "E21") (pin "1") (pinfunction "OE_1") (pintype "input"))
      (node (ref "E21") (pin "10") (pinfunction "OE_10") (pintype "input"))
      (node (ref "E21") (pin "13") (pinfunction "OE_13") (pintype "input"))
      (node (ref "E21") (pin "4") (pinfunction "OE_4") (pintype "input"))
      (node (ref "E8") (pin "1") (pinfunction "OE_1") (pintype "input"))
      (node (ref "E8") (pin "10") (pinfunction "OE_10") (pintype "input"))
      (node (ref "E8") (pin "13") (pinfunction "OE_13") (pintype "input"))
      (node (ref "E8") (pin "4") (pinfunction "OE_4") (pintype "input"))
    )
    (net (code "120") (name "unconnected-(E6A-~{Q1}-Pad1)") (class "Default")
      (node (ref "E6") (pin "1") (pinfunction "~{Q1}_1") (pintype "output"))
    )
    (net (code "121") (name "unconnected-(E6A-~{Q2}-Pad14)") (class "Default")
      (node (ref "E6") (pin "14") (pinfunction "~{Q2}_14") (pintype "output"))
    )
    (net (code "122") (name "unconnected-(E6A-~{Q3}-Pad11)") (class "Default")
      (node (ref "E6") (pin "11") (pinfunction "~{Q3}_11") (pintype "output"))
    )
    (net (code "123") (name "unconnected-(E6A-~{Q4}-Pad8)") (class "Default")
      (node (ref "E6") (pin "8") (pinfunction "~{Q4}_8") (pintype "output"))
    )
    (net (code "124") (name "unconnected-(E13A-~{Q1}-Pad1)") (class "Default")
      (node (ref "E13") (pin "1") (pinfunction "~{Q1}_1") (pintype "output"))
    )
    (net (code "125") (name "unconnected-(E13A-~{Q2}-Pad14)") (class "Default")
      (node (ref "E13") (pin "14") (pinfunction "~{Q2}_14") (pintype "output"))
    )
    (net (code "126") (name "unconnected-(E13A-~{Q3}-Pad11)") (class "Default")
      (node (ref "E13") (pin "11") (pinfunction "~{Q3}_11") (pintype "output"))
    )
    (net (code "127") (name "unconnected-(E13A-~{Q4}-Pad8)") (class "Default")
      (node (ref "E13") (pin "8") (pinfunction "~{Q4}_8") (pintype "output"))
    )
    (net (code "128") (name "unconnected-(E17A-~{Q1}-Pad1)") (class "Default")
      (node (ref "E17") (pin "1") (pinfunction "~{Q1}_1") (pintype "output"))
    )
    (net (code "129") (name "unconnected-(E17A-~{Q2}-Pad14)") (class "Default")
      (node (ref "E17") (pin "14") (pinfunction "~{Q2}_14") (pintype "output"))
    )
    (net (code "130") (name "unconnected-(E17A-~{Q3}-Pad11)") (class "Default")
      (node (ref "E17") (pin "11") (pinfunction "~{Q3}_11") (pintype "output"))
    )
    (net (code "131") (name "unconnected-(E17A-~{Q4}-Pad8)") (class "Default")
      (node (ref "E17") (pin "8") (pinfunction "~{Q4}_8") (pintype "output"))
    )
    (net (code "132") (name "unconnected-(E18B-~{Q}-Pad12)") (class "Default")
      (node (ref "E18") (pin "12") (pinfunction "~{Q}_12") (pintype "output"))
    )
    (net (code "133") (name "unconnected-(IC1-Pad3)") (class "Default")
      (node (ref "IC1") (pin "3") (pinfunction "3_3") (pintype "passive"))
    )
    (net (code "134") (name "unconnected-(IC1-Pad5)") (class "Default")
      (node (ref "IC1") (pin "5") (pinfunction "5_5") (pintype "passive"))
    )
    (net (code "135") (name "unconnected-(IC1-Pad7)") (class "Default")
      (node (ref "IC1") (pin "7") (pinfunction "7_7") (pintype "passive"))
    )
    (net (code "136") (name "~{VCC}") (class "Default")
      (node (ref "E15") (pin "20") (pinfunction "~{CE}_20") (pintype "input"))
      (node (ref "E16") (pin "20") (pinfunction "~{CE}_20") (pintype "input"))
      (node (ref "IC1") (pin "6") (pinfunction "6_6") (pintype "passive"))
    )
    (net (code "137") (name "~{WRITEP}") (class "Default")
      (node (ref "E12") (pin "13") (pinfunction "O_13") (pintype "output"))
      (node (ref "E15") (pin "27") (pinfunction "~{WE}_27") (pintype "input"))
      (node (ref "E16") (pin "27") (pinfunction "~{WE}_27") (pintype "input"))
    )
  )
)
